# FTDI_interface.net
KiCad netlist of a schematic drawn in Altium Designer
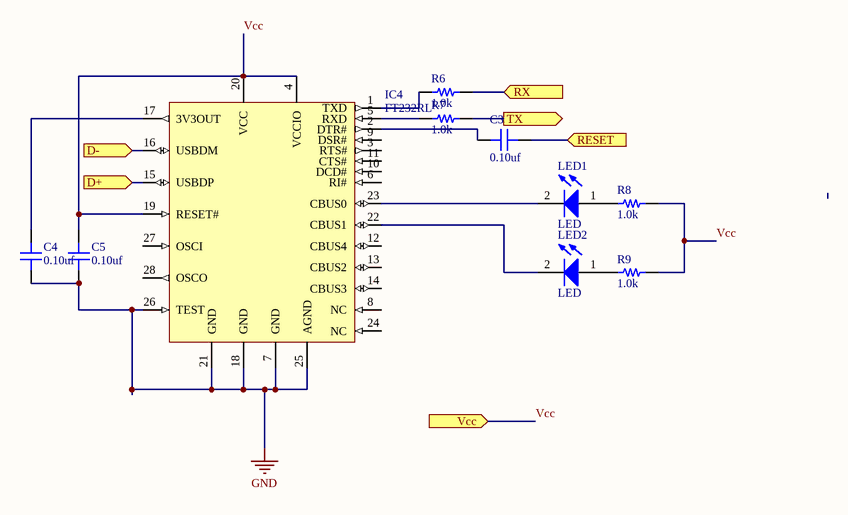
[diagram p0: FTDI_interface.SchDoc]

(export (version "E")
  (design (tool "Eeschema 10.0.6"))
  (components
    (comp (ref "C3")
      (value "0.10uf")
      (footprint "CAP 0805/2012")
      (fields
        (field (name "Comment") "Capacitor MLCC 0.10uf 16V CAP 0805/2012")
        (field (name "CREATED_BY") "Nick Mah")
      )
      (libsource (lib "Altium-Lib") (part "Capacitor"))
    )
    (comp (ref "C4")
      (value "0.10uf")
      (footprint "CAP 0805/2012")
      (fields
        (field (name "Comment") "Capacitor MLCC 0.10uf 16V CAP 0805/2012")
        (field (name "CREATED_BY") "Nick Mah")
      )
      (libsource (lib "Altium-Lib") (part "Capacitor"))
    )
    (comp (ref "C5")
      (value "0.10uf")
      (footprint "CAP 0805/2012")
      (fields
        (field (name "Comment") "Capacitor MLCC 0.10uf 16V CAP 0805/2012")
        (field (name "CREATED_BY") "Nick Mah")
      )
      (libsource (lib "Altium-Lib") (part "Capacitor"))
    )
    (comp (ref "IC4")
      (value "FT232RL")
      (footprint "SSOP-28")
      (fields (field (name "CREATED_BY") "Kyle"))
      (libsource (lib "Altium-Lib") (part "FT232RL"))
    )
    (comp (ref "LED1") (value "LED") (footprint "0805_LED") (libsource (lib "Altium-Lib") (part "LED")))
    (comp (ref "LED2") (value "LED") (footprint "0805_LED") (libsource (lib "Altium-Lib") (part "LED")))
    (comp (ref "R6")
      (value "1.0k")
      (footprint "RES 0805/2012")
      (fields
        (field (name "TOLERANCE") "1%")
        (field (name "POWER") "1/4W")
        (field (name "Comment") "Resistor 1.0k 0805 1/4W 1%")
        (field (name "CREATED_BY") "Nick Mah")
      )
      (libsource (lib "Altium-Lib") (part "Resistor"))
    )
    (comp (ref "R7")
      (value "1.0k")
      (footprint "RES 0805/2012")
      (fields
        (field (name "TOLERANCE") "1%")
        (field (name "POWER") "1/4W")
        (field (name "Comment") "Resistor 1.0k 0805 1/4W 1%")
        (field (name "CREATED_BY") "Nick Mah")
      )
      (libsource (lib "Altium-Lib") (part "Resistor"))
    )
    (comp (ref "R8")
      (value "1.0k")
      (footprint "RES 0805/2012")
      (fields
        (field (name "TOLERANCE") "1%")
        (field (name "POWER") "1/4W")
        (field (name "Comment") "Resistor 1.0k 0805 1/4W 1%")
        (field (name "CREATED_BY") "Nick Mah")
      )
      (libsource (lib "Altium-Lib") (part "Resistor"))
    )
    (comp (ref "R9")
      (value "1.0k")
      (footprint "RES 0805/2012")
      (fields
        (field (name "TOLERANCE") "1%")
        (field (name "POWER") "1/4W")
        (field (name "Comment") "Resistor 1.0k 0805 1/4W 1%")
        (field (name "CREATED_BY") "Nick Mah")
      )
      (libsource (lib "Altium-Lib") (part "Resistor"))
    )
  )
  (nets
    (net (code "1") (name "/D+") (class "Default")
      (node (ref "IC4") (pin "15") (pinfunction "USBDP_15") (pintype "bidirectional"))
    )
    (net (code "2") (name "/D-") (class "Default")
      (node (ref "IC4") (pin "16") (pinfunction "USBDM_16") (pintype "bidirectional"))
    )
    (net (code "3") (name "/RESET") (class "Default")
      (node (ref "C3") (pin "2") (pinfunction "2_2") (pintype "passive"))
    )
    (net (code "4") (name "/RX") (class "Default")
      (node (ref "R6") (pin "2") (pinfunction "2_2") (pintype "passive"))
    )
    (net (code "5") (name "/TX") (class "Default")
      (node (ref "R7") (pin "2") (pinfunction "2_2") (pintype "passive"))
    )
    (net (code "6") (name "/Vcc") (class "Default")
      (node (ref "C5") (pin "2") (pinfunction "2_2") (pintype "passive"))
      (node (ref "IC4") (pin "19") (pinfunction "RESET#_19") (pintype "input"))
      (node (ref "IC4") (pin "20") (pinfunction "VCC_20") (pintype "passive"))
      (node (ref "IC4") (pin "4") (pinfunction "VCCIO_4") (pintype "passive"))
      (node (ref "R8") (pin "2") (pinfunction "2_2") (pintype "passive"))
      (node (ref "R9") (pin "2") (pinfunction "2_2") (pintype "passive"))
    )
    (net (code "7") (name "GND") (class "Default")
      (node (ref "C4") (pin "1") (pinfunction "1_1") (pintype "passive"))
      (node (ref "C5") (pin "1") (pinfunction "1_1") (pintype "passive"))
      (node (ref "IC4") (pin "18") (pinfunction "GND_18") (pintype "passive"))
      (node (ref "IC4") (pin "21") (pinfunction "GND_21") (pintype "passive"))
      (node (ref "IC4") (pin "25") (pinfunction "AGND_25") (pintype "passive"))
      (node (ref "IC4") (pin "26") (pinfunction "TEST_26") (pintype "input"))
      (node (ref "IC4") (pin "7") (pinfunction "GND_7") (pintype "passive"))
    )
    (net (code "8") (name "Net-(IC4-3V3OUT)") (class "Default")
      (node (ref "C4") (pin "2") (pinfunction "2_2") (pintype "passive"))
      (node (ref "IC4") (pin "17") (pinfunction "3V3OUT_17") (pintype "output"))
    )
    (net (code "9") (name "Net-(IC4-CBUS0)") (class "Default")
      (node (ref "IC4") (pin "23") (pinfunction "CBUS0_23") (pintype "bidirectional"))
      (node (ref "LED1") (pin "2") (pinfunction "K_2") (pintype "passive"))
    )
    (net (code "10") (name "Net-(IC4-CBUS1)") (class "Default")
      (node (ref "IC4") (pin "22") (pinfunction "CBUS1_22") (pintype "bidirectional"))
      (node (ref "LED2") (pin "2") (pinfunction "K_2") (pintype "passive"))
    )
    (net (code "11") (name "Net-(IC4-DTR#)") (class "Default")
      (node (ref "C3") (pin "1") (pinfunction "1_1") (pintype "passive"))
      (node (ref "IC4") (pin "2") (pinfunction "DTR#_2") (pintype "output"))
    )
    (net (code "12") (name "Net-(IC4-RXD)") (class "Default")
      (node (ref "IC4") (pin "5") (pinfunction "RXD_5") (pintype "input"))
      (node (ref "R7") (pin "1") (pinfunction "1_1") (pintype "passive"))
    )
    (net (code "13") (name "Net-(IC4-TXD)") (class "Default")
      (node (ref "IC4") (pin "1") (pinfunction "TXD_1") (pintype "output"))
      (node (ref "R6") (pin "1") (pinfunction "1_1") (pintype "passive"))
    )
    (net (code "14") (name "Net-(LED1-A)") (class "Default")
      (node (ref "LED1") (pin "1") (pinfunction "A_1") (pintype "passive"))
      (node (ref "R8") (pin "1") (pinfunction "1_1") (pintype "passive"))
    )
    (net (code "15") (name "Net-(LED2-A)") (class "Default")
      (node (ref "LED2") (pin "1") (pinfunction "A_1") (pintype "passive"))
      (node (ref "R9") (pin "1") (pinfunction "1_1") (pintype "passive"))
    )
    (net (code "16") (name "unconnected-(IC4-CBUS2-Pad13)") (class "Default")
      (node (ref "IC4") (pin "13") (pinfunction "CBUS2_13") (pintype "bidirectional"))
    )
    (net (code "17") (name "unconnected-(IC4-CBUS3-Pad14)") (class "Default")
      (node (ref "IC4") (pin "14") (pinfunction "CBUS3_14") (pintype "bidirectional"))
    )
    (net (code "18") (name "unconnected-(IC4-CBUS4-Pad12)") (class "Default")
      (node (ref "IC4") (pin "12") (pinfunction "CBUS4_12") (pintype "bidirectional"))
    )
    (net (code "19") (name "unconnected-(IC4-CTS#-Pad11)") (class "Default")
      (node (ref "IC4") (pin "11") (pinfunction "CTS#_11") (pintype "input"))
    )
    (net (code "20") (name "unconnected-(IC4-DCD#-Pad10)") (class "Default")
      (node (ref "IC4") (pin "10") (pinfunction "DCD#_10") (pintype "input"))
    )
    (net (code "21") (name "unconnected-(IC4-DSR#-Pad9)") (class "Default")
      (node (ref "IC4") (pin "9") (pinfunction "DSR#_9") (pintype "input"))
    )
    (net (code "22") (name "unconnected-(IC4-NC-Pad8)") (class "Default")
      (node (ref "IC4") (pin "8") (pinfunction "NC_8") (pintype "input"))
    )
    (net (code "23") (name "unconnected-(IC4-NC-Pad24)") (class "Default")
      (node (ref "IC4") (pin "24") (pinfunction "NC_24") (pintype "input"))
    )
    (net (code "24") (name "unconnected-(IC4-OSCI-Pad27)") (class "Default")
      (node (ref "IC4") (pin "27") (pinfunction "OSCI_27") (pintype "input"))
    )
    (net (code "25") (name "unconnected-(IC4-OSCO-Pad28)") (class "Default")
      (node (ref "IC4") (pin "28") (pinfunction "OSCO_28") (pintype "output"))
    )
    (net (code "26") (name "unconnected-(IC4-RI#-Pad6)") (class "Default")
      (node (ref "IC4") (pin "6") (pinfunction "RI#_6") (pintype "input"))
    )
    (net (code "27") (name "unconnected-(IC4-RTS#-Pad3)") (class "Default")
      (node (ref "IC4") (pin "3") (pinfunction "RTS#_3") (pintype "output"))
    )
  )
)
